# ISP_POGO_programmer.net
KiCad netlist of a schematic drawn in EAGLE
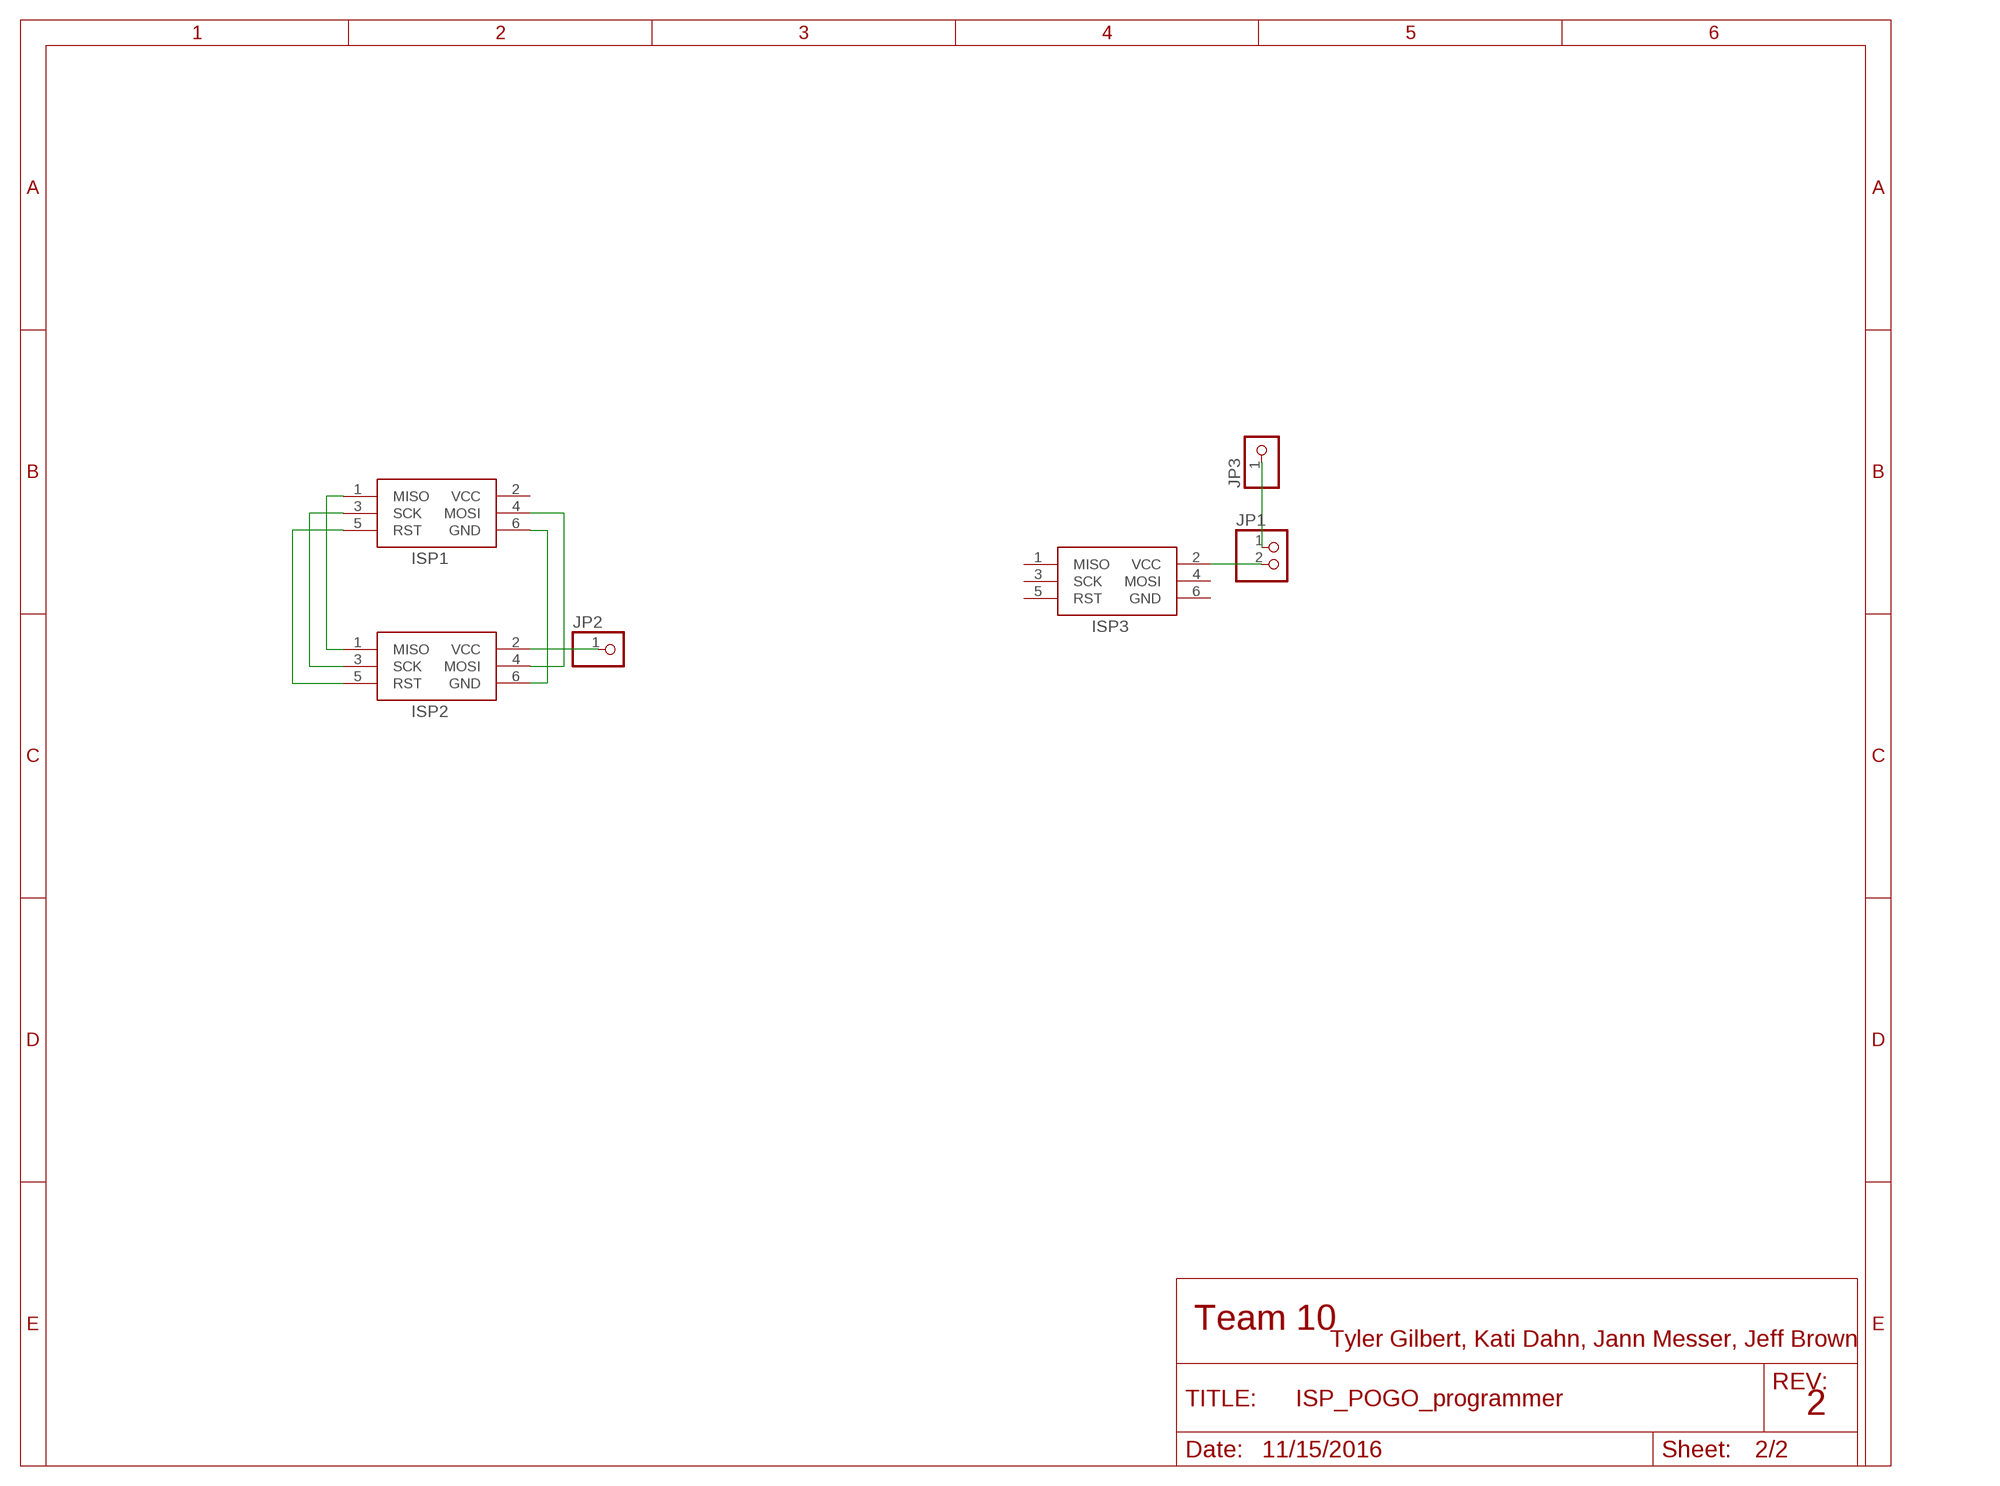
[diagram p0: schematic, sheet 1]

(export (version "E")
  (design (tool "Eeschema 10.0.6"))
  (components
    (comp (ref "ISP1")
      (value "AVRISP-6")
      (footprint "eagle-import:AVRISP")
      (libsource (lib "eagle-import") (part "AVRISP-6"))
    )
    (comp (ref "ISP2")
      (value "AVRISP-6")
      (footprint "eagle-import:AVRISP")
      (libsource (lib "eagle-import") (part "AVRISP-6"))
    )
    (comp (ref "ISP3")
      (value "AVRISP-6")
      (footprint "eagle-import:AVRISP")
      (libsource (lib "eagle-import") (part "AVRISP-6"))
    )
    (comp (ref "JP1")
      (value "PINHD-1X2")
      (footprint "eagle-import:1X02")
      (libsource (lib "eagle-import") (part "PINHD-1X2"))
    )
    (comp (ref "JP2")
      (value "PINHD-1X1")
      (footprint "eagle-import:1X01")
      (libsource (lib "eagle-import") (part "PINHD-1X1"))
    )
    (comp (ref "JP3")
      (value "PINHD-1X1")
      (footprint "eagle-import:1X01")
      (libsource (lib "eagle-import") (part "PINHD-1X1"))
    )
  )
  (nets
    (net (code "1") (name "/GND") (class "Default")
      (node (ref "ISP3") (pin "6") (pinfunction "GND_6") (pintype "power_in"))
    )
    (net (code "2") (name "/VCC") (class "Default")
      (node (ref "ISP1") (pin "2") (pinfunction "VCC_2") (pintype "power_in"))
    )
    (net (code "3") (name "Net-(ISP1-GND)") (class "Default")
      (node (ref "ISP1") (pin "6") (pinfunction "GND_6") (pintype "power_in"))
      (node (ref "ISP2") (pin "6") (pinfunction "GND_6") (pintype "power_in"))
    )
    (net (code "4") (name "Net-(ISP1-MISO)") (class "Default")
      (node (ref "ISP1") (pin "1") (pinfunction "MISO_1") (pintype "input"))
      (node (ref "ISP2") (pin "1") (pinfunction "MISO_1") (pintype "input"))
    )
    (net (code "5") (name "Net-(ISP1-MOSI)") (class "Default")
      (node (ref "ISP1") (pin "4") (pinfunction "MOSI_4") (pintype "output"))
      (node (ref "ISP2") (pin "4") (pinfunction "MOSI_4") (pintype "output"))
    )
    (net (code "6") (name "Net-(ISP1-RST)") (class "Default")
      (node (ref "ISP1") (pin "5") (pinfunction "RST_5") (pintype "output"))
      (node (ref "ISP2") (pin "5") (pinfunction "RST_5") (pintype "output"))
    )
    (net (code "7") (name "Net-(ISP1-SCK)") (class "Default")
      (node (ref "ISP1") (pin "3") (pinfunction "SCK_3") (pintype "output"))
      (node (ref "ISP2") (pin "3") (pinfunction "SCK_3") (pintype "output"))
    )
    (net (code "8") (name "Net-(ISP2-VCC)") (class "Default")
      (node (ref "ISP2") (pin "2") (pinfunction "VCC_2") (pintype "power_in"))
      (node (ref "JP2") (pin "1") (pinfunction "1_1") (pintype "passive"))
    )
    (net (code "9") (name "Net-(ISP3-VCC)") (class "Default")
      (node (ref "ISP3") (pin "2") (pinfunction "VCC_2") (pintype "power_in"))
      (node (ref "JP1") (pin "2") (pinfunction "2_2") (pintype "passive"))
    )
    (net (code "10") (name "Net-(JP1-Pad1)") (class "Default")
      (node (ref "JP1") (pin "1") (pinfunction "1_1") (pintype "passive"))
      (node (ref "JP3") (pin "1") (pinfunction "1_1") (pintype "passive"))
    )
    (net (code "11") (name "unconnected-(ISP3-MISO-Pad1)") (class "Default")
      (node (ref "ISP3") (pin "1") (pinfunction "MISO_1") (pintype "input"))
    )
    (net (code "12") (name "unconnected-(ISP3-MOSI-Pad4)") (class "Default")
      (node (ref "ISP3") (pin "4") (pinfunction "MOSI_4") (pintype "output"))
    )
    (net (code "13") (name "unconnected-(ISP3-RST-Pad5)") (class "Default")
      (node (ref "ISP3") (pin "5") (pinfunction "RST_5") (pintype "output"))
    )
    (net (code "14") (name "unconnected-(ISP3-SCK-Pad3)") (class "Default")
      (node (ref "ISP3") (pin "3") (pinfunction "SCK_3") (pintype "output"))
    )
  )
)
